# 06_Gyro.net
KiCad netlist of a schematic drawn in Altium Designer
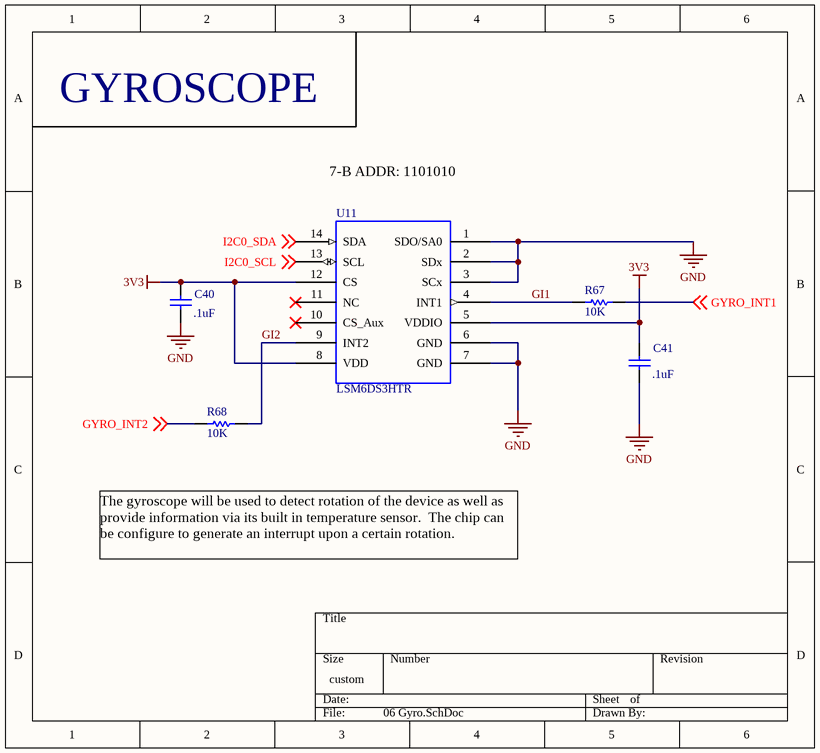
[diagram p0: 06 Gyro.SchDoc]

(export (version "E")
  (design (tool "Eeschema 10.0.6"))
  (components
    (comp (ref "C40")
      (value ".1uF")
      (footprint "CAPC2012X135N")
      (description "Cap Ceramic 0.1uF 250V X7T 10% SMD 0805 125C Plastic T/R")
      (fields
        (field (name "MANUFACTURER") "TDK")
        (field (name "MANUFACTURER PART NUMBER") "C2012X7T2E104K125AE")
      )
      (libsource (lib "schlib_truman") (part "CAP_0805_.1u_250V"))
    )
    (comp (ref "C41")
      (value ".1uF")
      (footprint "CAPC2012X135N")
      (description "Cap Ceramic 0.1uF 250V X7T 10% SMD 0805 125C Plastic T/R")
      (fields
        (field (name "MANUFACTURER") "TDK")
        (field (name "MANUFACTURER PART NUMBER") "C2012X7T2E104K125AE")
      )
      (libsource (lib "schlib_truman") (part "CAP_0805_.1u_250V"))
    )
    (comp (ref "R67")
      (value "RES_0805_10K")
      (footprint "RES0805")
      (description "RES, THICK FILM, 10K, 5%, 0.125W, 0805")
      (fields
        (field (name "MANUFACTURER") "Yageo")
        (field (name "MANUFACTURER PART NUMBER") "RC0805JR-0710KL")
        (field (name "RESISTANCE") "10K")
      )
      (libsource (lib "schlib_truman") (part "RES_0805_10K"))
    )
    (comp (ref "R68")
      (value "RES_0805_10K")
      (footprint "RES0805")
      (description "RES, THICK FILM, 10K, 5%, 0.125W, 0805")
      (fields
        (field (name "MANUFACTURER") "Yageo")
        (field (name "MANUFACTURER PART NUMBER") "RC0805JR-0710KL")
        (field (name "RESISTANCE") "10K")
      )
      (libsource (lib "schlib_truman") (part "RES_0805_10K"))
    )
    (comp (ref "U11")
      (value "LSM6DS3HTR")
      (footprint "PQFN50P300X250X86_HS-15N")
      (description "Accelerometer and Gyroscope 14-Pin LGA T/R")
      (fields (field (name "MANUFACTURER") "STMicroelectronics"))
      (libsource (lib "schlib_truman") (part "LSM6DS3HTR"))
    )
  )
  (nets
    (net (code "2") (name "/GI1") (class "Default")
      (node (ref "R67") (pin "1") (pinfunction "1_1") (pintype "passive"))
      (node (ref "U11") (pin "4") (pinfunction "INT1_4") (pintype "output"))
    )
    (net (code "3") (name "/GI2") (class "Default")
      (node (ref "R68") (pin "2") (pinfunction "2_2") (pintype "passive"))
      (node (ref "U11") (pin "9") (pinfunction "INT2_9") (pintype "passive"))
    )
    (net (code "4") (name "3V3") (class "Default")
      (node (ref "C40") (pin "2") (pinfunction "2_2") (pintype "passive"))
      (node (ref "C41") (pin "2") (pinfunction "2_2") (pintype "passive"))
      (node (ref "U11") (pin "12") (pinfunction "CS_12") (pintype "passive"))
      (node (ref "U11") (pin "5") (pinfunction "VDDIO_5") (pintype "power_in"))
      (node (ref "U11") (pin "8") (pinfunction "VDD_8") (pintype "power_in"))
    )
    (net (code "5") (name "GND") (class "Default")
      (node (ref "C40") (pin "1") (pinfunction "1_1") (pintype "passive"))
      (node (ref "C41") (pin "1") (pinfunction "1_1") (pintype "passive"))
      (node (ref "U11") (pin "1") (pinfunction "SDO/SA0_1") (pintype "passive"))
      (node (ref "U11") (pin "2") (pinfunction "SDx_2") (pintype "passive"))
      (node (ref "U11") (pin "3") (pinfunction "SCx_3") (pintype "passive"))
      (node (ref "U11") (pin "6") (pinfunction "GND_6") (pintype "power_in"))
      (node (ref "U11") (pin "7") (pinfunction "GND_7") (pintype "power_in"))
    )
    (net (code "6") (name "GYRO_INT1") (class "Default")
      (node (ref "R67") (pin "2") (pinfunction "2_2") (pintype "passive"))
    )
    (net (code "7") (name "GYRO_INT2") (class "Default")
      (node (ref "R68") (pin "1") (pinfunction "1_1") (pintype "passive"))
    )
    (net (code "8") (name "I2C0_SCL") (class "Default")
      (node (ref "U11") (pin "13") (pinfunction "SCL_13") (pintype "bidirectional"))
    )
    (net (code "9") (name "I2C0_SDA") (class "Default")
      (node (ref "U11") (pin "14") (pinfunction "SDA_14") (pintype "input"))
    )
    (net (code "10") (name "unconnected-(U11-CS_Aux-Pad10)") (class "Default")
      (node (ref "U11") (pin "10") (pinfunction "CS_Aux_10") (pintype "passive+no_connect"))
    )
    (net (code "11") (name "unconnected-(U11-NC-Pad11)") (class "Default")
      (node (ref "U11") (pin "11") (pinfunction "NC_11") (pintype "passive+no_connect"))
    )
  )
)
